# Motor.net
KiCad netlist of a schematic drawn in Altium Designer
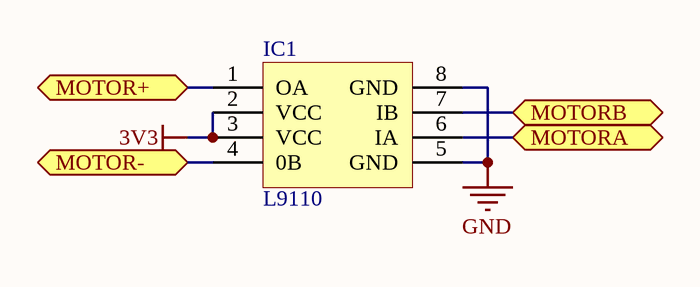
[diagram p0: Motor.SchDoc]

(export (version "E")
  (design (tool "Eeschema 10.0.6"))
  (components
    (comp (ref "IC1")
      (value "L9110")
      (footprint "SOP8_N")
      (description "直流电机控制芯片")
      (fields (field (name "版权归属") "封装库来自淘宝 ID：黄晶宝石"))
      (libsource (lib "1.0 - 常见芯片") (part "L9110"))
    )
  )
  (nets
    (net (code "1") (name "/MOTOR+") (class "Default")
      (node (ref "IC1") (pin "1") (pinfunction "OA_1") (pintype "passive"))
    )
    (net (code "2") (name "/MOTOR-") (class "Default")
      (node (ref "IC1") (pin "4") (pinfunction "0B_4") (pintype "passive"))
    )
    (net (code "3") (name "/MOTORA") (class "Default")
      (node (ref "IC1") (pin "6") (pinfunction "IA_6") (pintype "passive"))
    )
    (net (code "4") (name "/MOTORB") (class "Default")
      (node (ref "IC1") (pin "7") (pinfunction "IB_7") (pintype "passive"))
    )
    (net (code "5") (name "3V3") (class "Default")
      (node (ref "IC1") (pin "2") (pinfunction "VCC_2") (pintype "passive"))
      (node (ref "IC1") (pin "3") (pinfunction "VCC_3") (pintype "passive"))
    )
    (net (code "6") (name "GND") (class "Default")
      (node (ref "IC1") (pin "5") (pinfunction "GND_5") (pintype "passive"))
      (node (ref "IC1") (pin "8") (pinfunction "GND_8") (pintype "passive"))
    )
  )
)
